# ltc1043-chop-mux.net
KiCad netlist of a schematic drawn in EAGLE
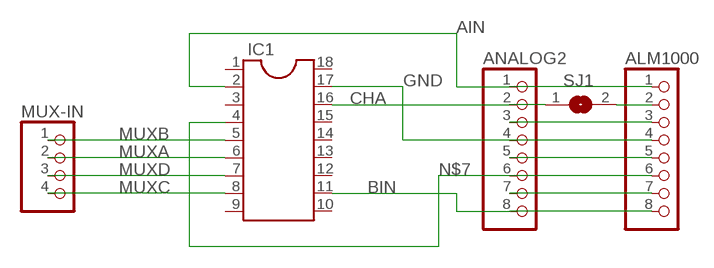
[diagram p0: schematic, sheet 1]

(export (version "E")
  (design (tool "Eeschema 10.0.6"))
  (components
    (comp (ref "ALM1000")
      (value "PINHD-1X8")
      (footprint "eagle-import:1X08")
      (libsource (lib "eagle-import") (part "PINHD-1X8"))
    )
    (comp (ref "ANALOG2")
      (value "PINHD-1X8")
      (footprint "eagle-import:1X08")
      (libsource (lib "eagle-import") (part "PINHD-1X8"))
    )
    (comp (ref "IC1")
      (value "DIL18")
      (footprint "eagle-import:DIL18")
      (libsource (lib "eagle-import") (part "DIL18"))
    )
    (comp (ref "MUX-IN")
      (value "PINHD-1X4")
      (footprint "eagle-import:1X04")
      (libsource (lib "eagle-import") (part "PINHD-1X4"))
    )
    (comp (ref "SJ1") (value "SJ") (footprint "eagle-import:SJ") (libsource (lib "eagle-import") (part "SJ")))
  )
  (nets
    (net (code "1") (name "/AIN") (class "Default")
      (node (ref "ALM1000") (pin "1") (pinfunction "1_1") (pintype "passive"))
      (node (ref "ANALOG2") (pin "1") (pinfunction "1_1") (pintype "passive"))
      (node (ref "IC1") (pin "2") (pinfunction "2_2") (pintype "passive"))
    )
    (net (code "2") (name "/BIN") (class "Default")
      (node (ref "ALM1000") (pin "8") (pinfunction "8_8") (pintype "passive"))
      (node (ref "ANALOG2") (pin "8") (pinfunction "8_8") (pintype "passive"))
      (node (ref "IC1") (pin "11") (pinfunction "11_11") (pintype "passive"))
    )
    (net (code "3") (name "/CHA") (class "Default")
      (node (ref "ANALOG2") (pin "2") (pinfunction "2_2") (pintype "passive"))
      (node (ref "IC1") (pin "16") (pinfunction "16_16") (pintype "passive"))
      (node (ref "SJ1") (pin "1") (pinfunction "1_1") (pintype "passive"))
    )
    (net (code "4") (name "/GND") (class "Default")
      (node (ref "ALM1000") (pin "4") (pinfunction "4_4") (pintype "passive"))
      (node (ref "ANALOG2") (pin "4") (pinfunction "4_4") (pintype "passive"))
      (node (ref "IC1") (pin "17") (pinfunction "17_17") (pintype "passive"))
    )
    (net (code "5") (name "/MUXA") (class "Default")
      (node (ref "IC1") (pin "6") (pinfunction "6_6") (pintype "passive"))
      (node (ref "MUX-IN") (pin "2") (pinfunction "2_2") (pintype "passive"))
    )
    (net (code "6") (name "/MUXB") (class "Default")
      (node (ref "IC1") (pin "5") (pinfunction "5_5") (pintype "passive"))
      (node (ref "MUX-IN") (pin "1") (pinfunction "1_1") (pintype "passive"))
    )
    (net (code "7") (name "/MUXC") (class "Default")
      (node (ref "IC1") (pin "8") (pinfunction "8_8") (pintype "passive"))
      (node (ref "MUX-IN") (pin "4") (pinfunction "4_4") (pintype "passive"))
    )
    (net (code "8") (name "/MUXD") (class "Default")
      (node (ref "IC1") (pin "7") (pinfunction "7_7") (pintype "passive"))
      (node (ref "MUX-IN") (pin "3") (pinfunction "3_3") (pintype "passive"))
    )
    (net (code "9") (name "/N$7") (class "Default")
      (node (ref "ALM1000") (pin "6") (pinfunction "6_6") (pintype "passive"))
      (node (ref "ANALOG2") (pin "6") (pinfunction "6_6") (pintype "passive"))
      (node (ref "IC1") (pin "4") (pinfunction "4_4") (pintype "passive"))
    )
    (net (code "10") (name "Net-(ALM1000-Pad2)") (class "Default")
      (node (ref "ALM1000") (pin "2") (pinfunction "2_2") (pintype "passive"))
      (node (ref "SJ1") (pin "2") (pinfunction "2_2") (pintype "passive"))
    )
    (net (code "11") (name "Net-(ALM1000-Pad3)") (class "Default")
      (node (ref "ALM1000") (pin "3") (pinfunction "3_3") (pintype "passive"))
      (node (ref "ANALOG2") (pin "3") (pinfunction "3_3") (pintype "passive"))
    )
    (net (code "12") (name "Net-(ALM1000-Pad5)") (class "Default")
      (node (ref "ALM1000") (pin "5") (pinfunction "5_5") (pintype "passive"))
      (node (ref "ANALOG2") (pin "5") (pinfunction "5_5") (pintype "passive"))
    )
    (net (code "13") (name "Net-(ALM1000-Pad7)") (class "Default")
      (node (ref "ALM1000") (pin "7") (pinfunction "7_7") (pintype "passive"))
      (node (ref "ANALOG2") (pin "7") (pinfunction "7_7") (pintype "passive"))
    )
    (net (code "14") (name "unconnected-(IC1-Pad1)") (class "Default")
      (node (ref "IC1") (pin "1") (pinfunction "1_1") (pintype "passive"))
    )
    (net (code "15") (name "unconnected-(IC1-Pad3)") (class "Default")
      (node (ref "IC1") (pin "3") (pinfunction "3_3") (pintype "passive"))
    )
    (net (code "16") (name "unconnected-(IC1-Pad9)") (class "Default")
      (node (ref "IC1") (pin "9") (pinfunction "9_9") (pintype "passive"))
    )
    (net (code "17") (name "unconnected-(IC1-Pad10)") (class "Default")
      (node (ref "IC1") (pin "10") (pinfunction "10_10") (pintype "passive"))
    )
    (net (code "18") (name "unconnected-(IC1-Pad12)") (class "Default")
      (node (ref "IC1") (pin "12") (pinfunction "12_12") (pintype "passive"))
    )
    (net (code "19") (name "unconnected-(IC1-Pad13)") (class "Default")
      (node (ref "IC1") (pin "13") (pinfunction "13_13") (pintype "passive"))
    )
    (net (code "20") (name "unconnected-(IC1-Pad14)") (class "Default")
      (node (ref "IC1") (pin "14") (pinfunction "14_14") (pintype "passive"))
    )
    (net (code "21") (name "unconnected-(IC1-Pad15)") (class "Default")
      (node (ref "IC1") (pin "15") (pinfunction "15_15") (pintype "passive"))
    )
    (net (code "22") (name "unconnected-(IC1-Pad18)") (class "Default")
      (node (ref "IC1") (pin "18") (pinfunction "18_18") (pintype "passive"))
    )
  )
)
